# ProPrj__AS5600_2025-07-28.net
KiCad netlist of a schematic drawn in EasyEDA Pro
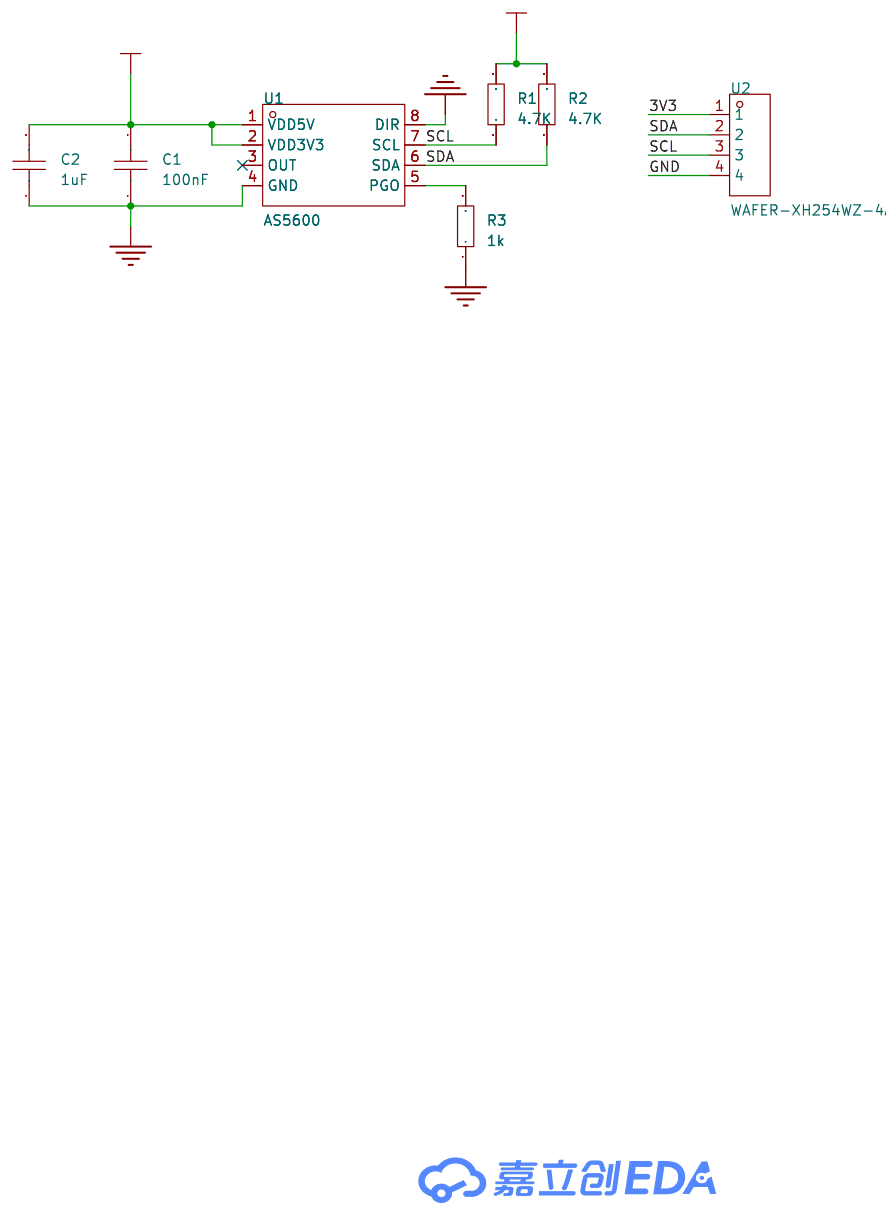
[diagram p0: schematic sheet]

(export (version "E")
  (design (tool "Eeschema 10.0.6"))
  (components
    (comp (ref "C1")
      (value "100nF")
      (footprint "easyedapro:C0603")
      (libsource (lib "easyedapro") (part "CapAcitance"))
    )
    (comp (ref "C2")
      (value "1uF")
      (footprint "easyedapro:C0603")
      (libsource (lib "easyedapro") (part "CapAcitance"))
    )
    (comp (ref "R1") (value "4.7K") (footprint "easyedapro:R0603") (libsource (lib "easyedapro") (part "电阻")))
    (comp (ref "R2") (value "4.7K") (footprint "easyedapro:R0603") (libsource (lib "easyedapro") (part "电阻")))
    (comp (ref "R3") (value "1k") (footprint "easyedapro:R0603") (libsource (lib "easyedapro") (part "电阻")))
    (comp (ref "U1")
      (value "AS5600")
      (footprint "easyedapro:SOIC-8_L4.9-W3.9-P1.27-LS6.0-BL")
      (libsource (lib "easyedapro") (part "AS5600"))
    )
    (comp (ref "U2")
      (value "WAFER-XH254WZ-4A")
      (footprint "easyedapro:CONN-TH_4P-P2.50_WAFER-XH254WZ-4A")
      (description "插针结构:1x4P;间距:2.54mm;安装方式:弯插;参考系列:XH;总PIN数:4P;排数:1;每排PIN数:4;额定电流:3A;触头材质:黄铜;工作温度:-25°C~+85°C;")
      (fields (field (name "Manufacturer") "HANBO(汉博)"))
      (libsource (lib "easyedapro") (part "WAFER-XH254WZ-4A"))
    )
  )
  (nets
    (net (code "1") (name "/SCL") (class "Default")
      (node (ref "R1") (pin "1") (pinfunction "1_1") (pintype "input"))
      (node (ref "U1") (pin "7") (pinfunction "SCL_7") (pintype "unspecified"))
      (node (ref "U2") (pin "3") (pinfunction "3_3") (pintype "unspecified"))
    )
    (net (code "2") (name "/SDA") (class "Default")
      (node (ref "R2") (pin "1") (pinfunction "1_1") (pintype "input"))
      (node (ref "U1") (pin "6") (pinfunction "SDA_6") (pintype "unspecified"))
      (node (ref "U2") (pin "2") (pinfunction "2_2") (pintype "unspecified"))
    )
    (net (code "3") (name "3V3") (class "Default")
      (node (ref "C1") (pin "2") (pinfunction "2_2") (pintype "input"))
      (node (ref "C2") (pin "2") (pinfunction "2_2") (pintype "input"))
      (node (ref "R1") (pin "2") (pinfunction "2_2") (pintype "input"))
      (node (ref "R2") (pin "2") (pinfunction "2_2") (pintype "input"))
      (node (ref "U1") (pin "1") (pinfunction "VDD5V_1") (pintype "unspecified"))
      (node (ref "U1") (pin "2") (pinfunction "VDD3V3_2") (pintype "unspecified"))
      (node (ref "U2") (pin "1") (pinfunction "1_1") (pintype "unspecified"))
    )
    (net (code "4") (name "GND") (class "Default")
      (node (ref "C1") (pin "1") (pinfunction "1_1") (pintype "input"))
      (node (ref "C2") (pin "1") (pinfunction "1_1") (pintype "input"))
      (node (ref "R3") (pin "1") (pinfunction "1_1") (pintype "input"))
      (node (ref "U1") (pin "4") (pinfunction "GND_4") (pintype "unspecified"))
      (node (ref "U1") (pin "8") (pinfunction "DIR_8") (pintype "unspecified"))
      (node (ref "U2") (pin "4") (pinfunction "4_4") (pintype "unspecified"))
    )
    (net (code "5") (name "Net-(U1-PGO)") (class "Default")
      (node (ref "R3") (pin "2") (pinfunction "2_2") (pintype "input"))
      (node (ref "U1") (pin "5") (pinfunction "PGO_5") (pintype "unspecified"))
    )
    (net (code "6") (name "unconnected-(U1-OUT-Pad3)") (class "Default")
      (node (ref "U1") (pin "3") (pinfunction "OUT_3") (pintype "unspecified+no_connect"))
    )
  )
)
